# GuitarPedal.net
KiCad netlist of a schematic drawn in Altium Designer
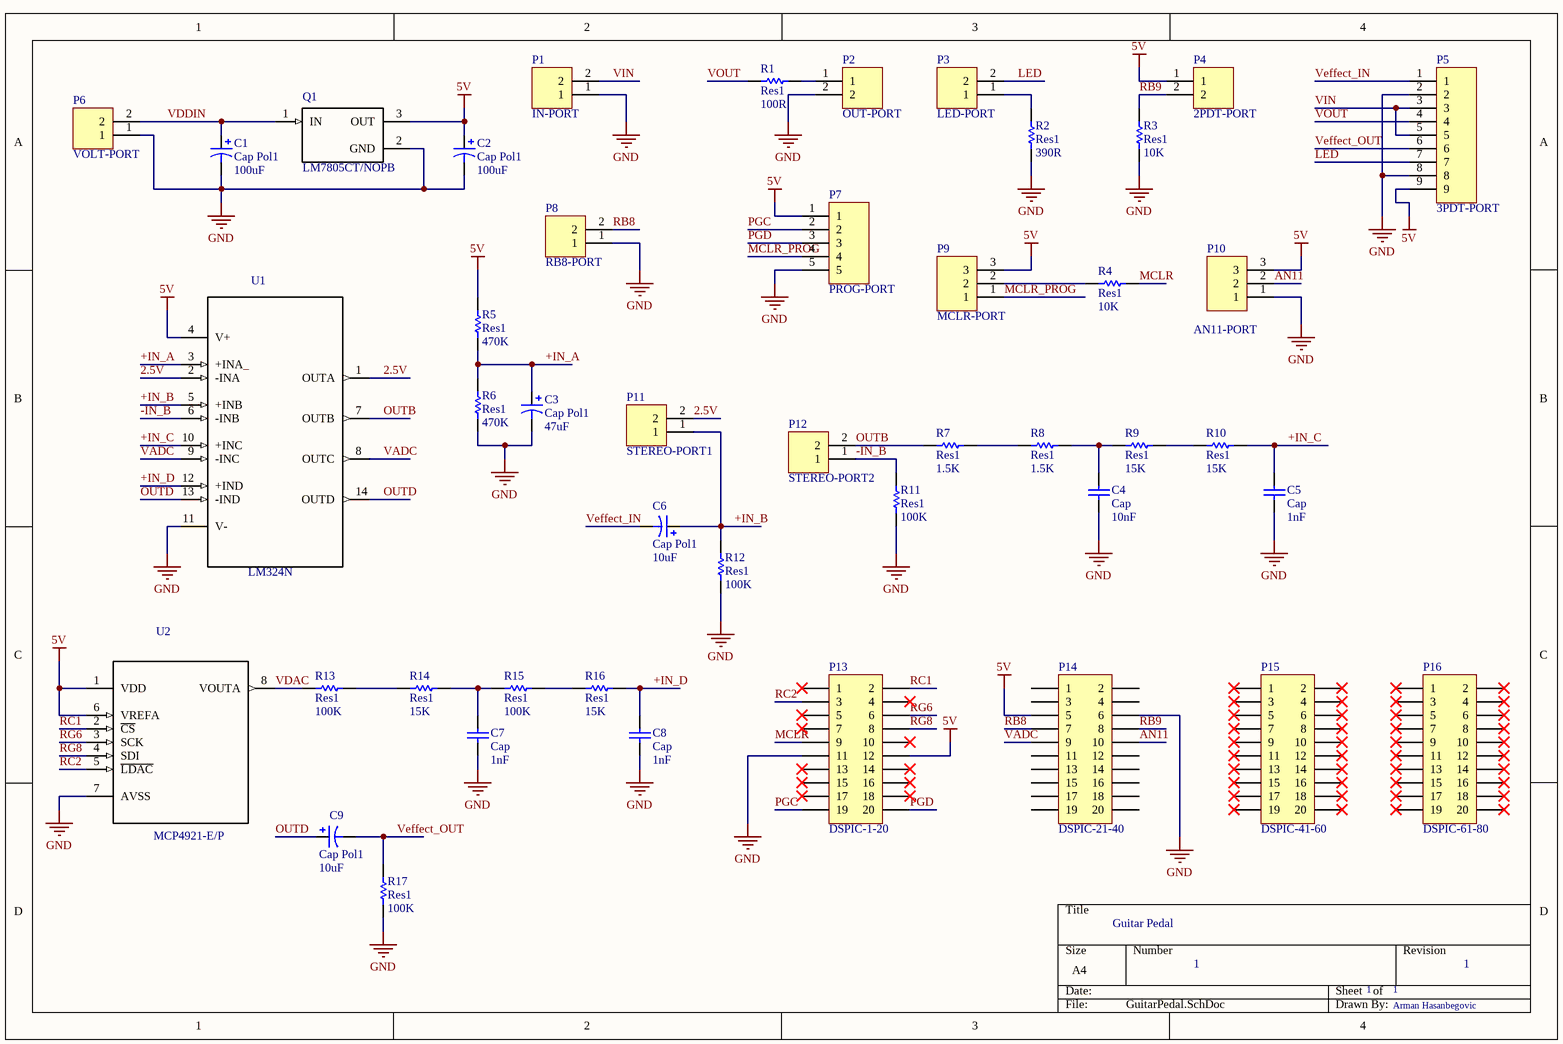
[diagram p0: GuitarPedal.SchDoc]

(export (version "E")
  (design (tool "Eeschema 10.0.6"))
  (components
    (comp (ref "C1")
      (value "Cap Pol1")
      (footprint "RB7.6-15")
      (description "Polarized Capacitor (Radial)")
      (fields (field (name "ALTIUM_VALUE") "100uF") (field (name "PUBLISHER") "Altium Limited"))
      (libsource (lib "Miscellaneous Devices") (part "Cap Pol1"))
    )
    (comp (ref "C2")
      (value "Cap Pol1")
      (footprint "RB7.6-15")
      (description "Polarized Capacitor (Radial)")
      (fields (field (name "ALTIUM_VALUE") "100uF") (field (name "PUBLISHER") "Altium Limited"))
      (libsource (lib "Miscellaneous Devices") (part "Cap Pol1"))
    )
    (comp (ref "C3")
      (value "Cap Pol1")
      (footprint "RB7.6-15")
      (description "Polarized Capacitor (Radial)")
      (fields (field (name "ALTIUM_VALUE") "47uF") (field (name "PUBLISHER") "Altium Limited"))
      (libsource (lib "Miscellaneous Devices") (part "Cap Pol1"))
    )
    (comp (ref "C4")
      (value "Cap")
      (footprint "RAD-0.3")
      (description "Capacitor")
      (fields (field (name "ALTIUM_VALUE") "10nF") (field (name "PUBLISHER") "Altium Limited"))
      (libsource (lib "Miscellaneous Devices") (part "Cap"))
    )
    (comp (ref "C5")
      (value "Cap")
      (footprint "RAD-0.3")
      (description "Capacitor")
      (fields (field (name "ALTIUM_VALUE") "1nF") (field (name "PUBLISHER") "Altium Limited"))
      (libsource (lib "Miscellaneous Devices") (part "Cap"))
    )
    (comp (ref "C6")
      (value "Cap Pol1")
      (footprint "RB7.6-15")
      (description "Polarized Capacitor (Radial)")
      (fields (field (name "ALTIUM_VALUE") "10uF") (field (name "PUBLISHER") "Altium Limited"))
      (libsource (lib "Miscellaneous Devices") (part "Cap Pol1"))
    )
    (comp (ref "C7")
      (value "Cap")
      (footprint "RAD-0.3")
      (description "Capacitor")
      (fields (field (name "ALTIUM_VALUE") "1nF") (field (name "PUBLISHER") "Altium Limited"))
      (libsource (lib "Miscellaneous Devices") (part "Cap"))
    )
    (comp (ref "C8")
      (value "Cap")
      (footprint "RAD-0.3")
      (description "Capacitor")
      (fields (field (name "ALTIUM_VALUE") "1nF") (field (name "PUBLISHER") "Altium Limited"))
      (libsource (lib "Miscellaneous Devices") (part "Cap"))
    )
    (comp (ref "C9")
      (value "Cap Pol1")
      (footprint "RB7.6-15")
      (description "Polarized Capacitor (Radial)")
      (fields (field (name "ALTIUM_VALUE") "10uF") (field (name "PUBLISHER") "Altium Limited"))
      (libsource (lib "Miscellaneous Devices") (part "Cap Pol1"))
    )
    (comp (ref "P1")
      (value "IN-PORT")
      (footprint "HDR1X2")
      (description "Header, 2-Pin")
      (fields (field (name "PUBLISHER") "Altium Limited"))
      (libsource (lib "Miscellaneous Connectors") (part "Header 2"))
    )
    (comp (ref "P2")
      (value "OUT-PORT")
      (footprint "HDR1X2")
      (description "Header, 2-Pin")
      (fields (field (name "PUBLISHER") "Altium Limited"))
      (libsource (lib "") (part "Header 2_1"))
    )
    (comp (ref "P3")
      (value "LED-PORT")
      (footprint "HDR1X2")
      (description "Header, 2-Pin")
      (fields (field (name "PUBLISHER") "Altium Limited"))
      (libsource (lib "Miscellaneous Connectors") (part "Header 2"))
    )
    (comp (ref "P4")
      (value "2PDT-PORT")
      (footprint "HDR1X2")
      (description "Header, 2-Pin")
      (fields (field (name "PUBLISHER") "Altium Limited"))
      (libsource (lib "") (part "Header 2_1"))
    )
    (comp (ref "P5")
      (value "3PDT-PORT")
      (footprint "HDR1X9")
      (description "Header, 9-Pin")
      (fields (field (name "PUBLISHER") "Altium Limited"))
      (libsource (lib "Miscellaneous Connectors") (part "Header 9"))
    )
    (comp (ref "P6")
      (value "VOLT-PORT")
      (footprint "HDR1X2")
      (description "Header, 2-Pin")
      (fields (field (name "PUBLISHER") "Altium Limited"))
      (libsource (lib "Miscellaneous Connectors") (part "Header 2"))
    )
    (comp (ref "P7")
      (value "PROG-PORT")
      (footprint "HDR1X5")
      (description "Header, 5-Pin")
      (fields (field (name "PUBLISHER") "Altium Limited"))
      (libsource (lib "Miscellaneous Connectors") (part "Header 5"))
    )
    (comp (ref "P8")
      (value "RB8-PORT")
      (footprint "HDR1X2")
      (description "Header, 2-Pin")
      (fields (field (name "PUBLISHER") "Altium Limited"))
      (libsource (lib "Miscellaneous Connectors") (part "Header 2"))
    )
    (comp (ref "P9")
      (value "MCLR-PORT")
      (footprint "HDR1X3")
      (description "Header, 3-Pin")
      (fields (field (name "PUBLISHER") "Altium Limited"))
      (libsource (lib "Miscellaneous Connectors") (part "Header 3"))
    )
    (comp (ref "P10")
      (value "AN11-PORT")
      (footprint "HDR1X3")
      (description "Header, 3-Pin")
      (fields (field (name "PUBLISHER") "Altium Limited"))
      (libsource (lib "Miscellaneous Connectors") (part "Header 3"))
    )
    (comp (ref "P11")
      (value "STEREO-PORT1")
      (footprint "HDR1X2")
      (description "Header, 2-Pin")
      (fields (field (name "PUBLISHER") "Altium Limited"))
      (libsource (lib "Miscellaneous Connectors") (part "Header 2"))
    )
    (comp (ref "P12")
      (value "STEREO-PORT2")
      (footprint "HDR1X2")
      (description "Header, 2-Pin")
      (fields (field (name "PUBLISHER") "Altium Limited"))
      (libsource (lib "Miscellaneous Connectors") (part "Header 2"))
    )
    (comp (ref "P13")
      (value "DSPIC-1-20")
      (footprint "HDR2X10")
      (description "Header, 10-Pin, Dual row")
      (fields (field (name "PUBLISHER") "Altium Limited"))
      (libsource (lib "Miscellaneous Connectors") (part "Header 10X2"))
    )
    (comp (ref "P14")
      (value "DSPIC-21-40")
      (footprint "HDR2X10")
      (description "Header, 10-Pin, Dual row")
      (fields (field (name "PUBLISHER") "Altium Limited"))
      (libsource (lib "Miscellaneous Connectors") (part "Header 10X2"))
    )
    (comp (ref "P15")
      (value "DSPIC-41-60")
      (footprint "HDR2X10")
      (description "Header, 10-Pin, Dual row")
      (fields (field (name "PUBLISHER") "Altium Limited"))
      (libsource (lib "Miscellaneous Connectors") (part "Header 10X2"))
    )
    (comp (ref "P16")
      (value "DSPIC-61-80")
      (footprint "HDR2X10")
      (description "Header, 10-Pin, Dual row")
      (fields (field (name "PUBLISHER") "Altium Limited"))
      (libsource (lib "Miscellaneous Connectors") (part "Header 10X2"))
    )
    (comp (ref "Q1")
      (value "LM7805CT/NOPB")
      (footprint "*TO254P1054X470X2600-3")
      (description "IC REG LINEAR 5V 1A TO220AB")
      (fields (field (name "MP") "LM7805CT") (field (name "MF") "ON Semiconductor"))
      (libsource (lib "LM7805CT_NOPB") (part "LM7805CT/NOPB"))
    )
    (comp (ref "R1")
      (value "Res1")
      (footprint "AXIAL-0.3")
      (description "Resistor")
      (fields (field (name "ALTIUM_VALUE") "100R") (field (name "PUBLISHER") "Altium Limited"))
      (libsource (lib "Miscellaneous Devices") (part "Res1"))
    )
    (comp (ref "R2")
      (value "Res1")
      (footprint "AXIAL-0.3")
      (description "Resistor")
      (fields (field (name "ALTIUM_VALUE") "390R") (field (name "PUBLISHER") "Altium Limited"))
      (libsource (lib "Miscellaneous Devices") (part "Res1"))
    )
    (comp (ref "R3")
      (value "Res1")
      (footprint "AXIAL-0.3")
      (description "Resistor")
      (fields (field (name "ALTIUM_VALUE") "10K") (field (name "PUBLISHER") "Altium Limited"))
      (libsource (lib "Miscellaneous Devices") (part "Res1"))
    )
    (comp (ref "R4")
      (value "Res1")
      (footprint "AXIAL-0.3")
      (description "Resistor")
      (fields (field (name "ALTIUM_VALUE") "10K") (field (name "PUBLISHER") "Altium Limited"))
      (libsource (lib "Miscellaneous Devices") (part "Res1"))
    )
    (comp (ref "R5")
      (value "Res1")
      (footprint "AXIAL-0.3")
      (description "Resistor")
      (fields (field (name "ALTIUM_VALUE") "470K") (field (name "PUBLISHER") "Altium Limited"))
      (libsource (lib "Miscellaneous Devices") (part "Res1"))
    )
    (comp (ref "R6")
      (value "Res1")
      (footprint "AXIAL-0.3")
      (description "Resistor")
      (fields (field (name "ALTIUM_VALUE") "470K") (field (name "PUBLISHER") "Altium Limited"))
      (libsource (lib "Miscellaneous Devices") (part "Res1"))
    )
    (comp (ref "R7")
      (value "Res1")
      (footprint "AXIAL-0.3")
      (description "Resistor")
      (fields (field (name "ALTIUM_VALUE") "1.5K") (field (name "PUBLISHER") "Altium Limited"))
      (libsource (lib "Miscellaneous Devices") (part "Res1"))
    )
    (comp (ref "R8")
      (value "Res1")
      (footprint "AXIAL-0.3")
      (description "Resistor")
      (fields (field (name "ALTIUM_VALUE") "1.5K") (field (name "PUBLISHER") "Altium Limited"))
      (libsource (lib "Miscellaneous Devices") (part "Res1"))
    )
    (comp (ref "R9")
      (value "Res1")
      (footprint "AXIAL-0.3")
      (description "Resistor")
      (fields (field (name "ALTIUM_VALUE") "15K") (field (name "PUBLISHER") "Altium Limited"))
      (libsource (lib "Miscellaneous Devices") (part "Res1"))
    )
    (comp (ref "R10")
      (value "Res1")
      (footprint "AXIAL-0.3")
      (description "Resistor")
      (fields (field (name "ALTIUM_VALUE") "15K") (field (name "PUBLISHER") "Altium Limited"))
      (libsource (lib "Miscellaneous Devices") (part "Res1"))
    )
    (comp (ref "R11")
      (value "Res1")
      (footprint "AXIAL-0.3")
      (description "Resistor")
      (fields (field (name "ALTIUM_VALUE") "100K") (field (name "PUBLISHER") "Altium Limited"))
      (libsource (lib "Miscellaneous Devices") (part "Res1"))
    )
    (comp (ref "R12")
      (value "Res1")
      (footprint "AXIAL-0.3")
      (description "Resistor")
      (fields (field (name "ALTIUM_VALUE") "100K") (field (name "PUBLISHER") "Altium Limited"))
      (libsource (lib "Miscellaneous Devices") (part "Res1"))
    )
    (comp (ref "R13")
      (value "Res1")
      (footprint "AXIAL-0.3")
      (description "Resistor")
      (fields (field (name "ALTIUM_VALUE") "100K") (field (name "PUBLISHER") "Altium Limited"))
      (libsource (lib "Miscellaneous Devices") (part "Res1"))
    )
    (comp (ref "R14")
      (value "Res1")
      (footprint "AXIAL-0.3")
      (description "Resistor")
      (fields (field (name "ALTIUM_VALUE") "15K") (field (name "PUBLISHER") "Altium Limited"))
      (libsource (lib "Miscellaneous Devices") (part "Res1"))
    )
    (comp (ref "R15")
      (value "Res1")
      (footprint "AXIAL-0.3")
      (description "Resistor")
      (fields (field (name "ALTIUM_VALUE") "100K") (field (name "PUBLISHER") "Altium Limited"))
      (libsource (lib "Miscellaneous Devices") (part "Res1"))
    )
    (comp (ref "R16")
      (value "Res1")
      (footprint "AXIAL-0.3")
      (description "Resistor")
      (fields (field (name "ALTIUM_VALUE") "15K") (field (name "PUBLISHER") "Altium Limited"))
      (libsource (lib "Miscellaneous Devices") (part "Res1"))
    )
    (comp (ref "R17")
      (value "Res1")
      (footprint "AXIAL-0.3")
      (description "Resistor")
      (fields (field (name "ALTIUM_VALUE") "100K") (field (name "PUBLISHER") "Altium Limited"))
      (libsource (lib "Miscellaneous Devices") (part "Res1"))
    )
    (comp (ref "U1")
      (value "LM324N")
      (footprint "*DIP254P762X508-14")
      (description "Ic Opamp Gp 1.2mhz 14dip")
      (fields (field (name "MF") "STMicroelectronics"))
      (libsource (lib "LM324N") (part "LM324N"))
    )
    (comp (ref "U2")
      (value "MCP4921-E/P")
      (footprint "*DIP254P762X432-8")
      (description "MCP4921 Series 1 Ch 12-Bit Voltage Output Digital-to-Analog Converter-PDIP-8")
      (fields (field (name "DIGI-KEY_PART_NUMBER") "MCP4921-E/P-ND") (field (name "MF") "Microchip"))
      (libsource (lib "MCP4921-E_P") (part "MCP4921-E/P"))
    )
  )
  (nets
    (net (code "1") (name "/+IN_A") (class "Default")
      (node (ref "C3") (pin "1") (pinfunction "1_1") (pintype "passive"))
      (node (ref "R5") (pin "1") (pinfunction "1_1") (pintype "passive"))
      (node (ref "R6") (pin "2") (pinfunction "2_2") (pintype "passive"))
      (node (ref "U1") (pin "3") (pinfunction "+INA__3") (pintype "input"))
    )
    (net (code "2") (name "/+IN_B") (class "Default")
      (node (ref "C6") (pin "1") (pinfunction "1_1") (pintype "passive"))
      (node (ref "P11") (pin "1") (pinfunction "1_1") (pintype "passive"))
      (node (ref "R12") (pin "2") (pinfunction "2_2") (pintype "passive"))
      (node (ref "U1") (pin "5") (pinfunction "+INB_5") (pintype "input"))
    )
    (net (code "3") (name "/+IN_C") (class "Default")
      (node (ref "C5") (pin "2") (pinfunction "2_2") (pintype "passive"))
      (node (ref "R10") (pin "2") (pinfunction "2_2") (pintype "passive"))
      (node (ref "U1") (pin "10") (pinfunction "+INC_10") (pintype "input"))
    )
    (net (code "4") (name "/+IN_D") (class "Default")
      (node (ref "C8") (pin "2") (pinfunction "2_2") (pintype "passive"))
      (node (ref "R16") (pin "2") (pinfunction "2_2") (pintype "passive"))
      (node (ref "U1") (pin "12") (pinfunction "+IND_12") (pintype "input"))
    )
    (net (code "5") (name "/-IN_B") (class "Default")
      (node (ref "P12") (pin "1") (pinfunction "1_1") (pintype "passive"))
      (node (ref "R11") (pin "2") (pinfunction "2_2") (pintype "passive"))
      (node (ref "U1") (pin "6") (pinfunction "-INB_6") (pintype "input"))
    )
    (net (code "6") (name "/2.5V") (class "Default")
      (node (ref "P11") (pin "2") (pinfunction "2_2") (pintype "passive"))
      (node (ref "U1") (pin "1") (pinfunction "OUTA_1") (pintype "output"))
      (node (ref "U1") (pin "2") (pinfunction "-INA_2") (pintype "input"))
    )
    (net (code "7") (name "/AN11") (class "Default")
      (node (ref "P10") (pin "2") (pinfunction "2_2") (pintype "passive"))
      (node (ref "P14") (pin "10") (pinfunction "10_10") (pintype "passive"))
    )
    (net (code "8") (name "/LED") (class "Default")
      (node (ref "P3") (pin "2") (pinfunction "2_2") (pintype "passive"))
      (node (ref "P5") (pin "7") (pinfunction "7_7") (pintype "passive"))
    )
    (net (code "9") (name "/MCLR") (class "Default")
      (node (ref "P13") (pin "9") (pinfunction "9_9") (pintype "passive"))
      (node (ref "R4") (pin "2") (pinfunction "2_2") (pintype "passive"))
    )
    (net (code "10") (name "/MCLR_PROG") (class "Default")
      (node (ref "P7") (pin "4") (pinfunction "4_4") (pintype "passive"))
      (node (ref "P9") (pin "1") (pinfunction "1_1") (pintype "passive"))
    )
    (net (code "11") (name "/OUTB") (class "Default")
      (node (ref "P12") (pin "2") (pinfunction "2_2") (pintype "passive"))
      (node (ref "R7") (pin "1") (pinfunction "1_1") (pintype "passive"))
      (node (ref "U1") (pin "7") (pinfunction "OUTB_7") (pintype "output"))
    )
    (net (code "12") (name "/OUTD") (class "Default")
      (node (ref "C9") (pin "1") (pinfunction "1_1") (pintype "passive"))
      (node (ref "U1") (pin "13") (pinfunction "-IND_13") (pintype "input"))
      (node (ref "U1") (pin "14") (pinfunction "OUTD_14") (pintype "output"))
    )
    (net (code "13") (name "/PGC") (class "Default")
      (node (ref "P13") (pin "19") (pinfunction "19_19") (pintype "passive"))
      (node (ref "P7") (pin "2") (pinfunction "2_2") (pintype "passive"))
    )
    (net (code "14") (name "/PGD") (class "Default")
      (node (ref "P13") (pin "20") (pinfunction "20_20") (pintype "passive"))
      (node (ref "P7") (pin "3") (pinfunction "3_3") (pintype "passive"))
    )
    (net (code "15") (name "/RB8") (class "Default")
      (node (ref "P14") (pin "7") (pinfunction "7_7") (pintype "passive"))
      (node (ref "P8") (pin "2") (pinfunction "2_2") (pintype "passive"))
    )
    (net (code "16") (name "/RB9") (class "Default")
      (node (ref "P14") (pin "8") (pinfunction "8_8") (pintype "passive"))
      (node (ref "P4") (pin "2") (pinfunction "2_2") (pintype "passive"))
      (node (ref "R3") (pin "2") (pinfunction "2_2") (pintype "passive"))
    )
    (net (code "17") (name "/RC1") (class "Default")
      (node (ref "P13") (pin "2") (pinfunction "2_2") (pintype "passive"))
      (node (ref "U2") (pin "2") (pinfunction "~{CS}_2") (pintype "input"))
    )
    (net (code "18") (name "/RC2") (class "Default")
      (node (ref "P13") (pin "3") (pinfunction "3_3") (pintype "passive"))
      (node (ref "U2") (pin "5") (pinfunction "~{LDAC}_5") (pintype "input"))
    )
    (net (code "19") (name "/RG6") (class "Default")
      (node (ref "P13") (pin "6") (pinfunction "6_6") (pintype "passive"))
      (node (ref "U2") (pin "3") (pinfunction "SCK_3") (pintype "input"))
    )
    (net (code "20") (name "/RG8") (class "Default")
      (node (ref "P13") (pin "8") (pinfunction "8_8") (pintype "passive"))
      (node (ref "U2") (pin "4") (pinfunction "SDI_4") (pintype "input"))
    )
    (net (code "21") (name "/VADC") (class "Default")
      (node (ref "P14") (pin "9") (pinfunction "9_9") (pintype "passive"))
      (node (ref "U1") (pin "8") (pinfunction "OUTC_8") (pintype "output"))
      (node (ref "U1") (pin "9") (pinfunction "-INC_9") (pintype "input"))
    )
    (net (code "22") (name "/VDAC") (class "Default")
      (node (ref "R13") (pin "1") (pinfunction "1_1") (pintype "passive"))
      (node (ref "U2") (pin "8") (pinfunction "VOUTA_8") (pintype "output"))
    )
    (net (code "23") (name "/VDDIN") (class "Default")
      (node (ref "C1") (pin "1") (pinfunction "1_1") (pintype "passive"))
      (node (ref "P6") (pin "2") (pinfunction "2_2") (pintype "passive"))
      (node (ref "Q1") (pin "1") (pinfunction "IN_1") (pintype "input"))
    )
    (net (code "24") (name "/VIN") (class "Default")
      (node (ref "P1") (pin "2") (pinfunction "2_2") (pintype "passive"))
      (node (ref "P5") (pin "3") (pinfunction "3_3") (pintype "passive"))
      (node (ref "P5") (pin "5") (pinfunction "5_5") (pintype "passive"))
    )
    (net (code "25") (name "/VOUT") (class "Default")
      (node (ref "P5") (pin "4") (pinfunction "4_4") (pintype "passive"))
      (node (ref "R1") (pin "1") (pinfunction "1_1") (pintype "passive"))
    )
    (net (code "26") (name "/Veffect_IN") (class "Default")
      (node (ref "C6") (pin "2") (pinfunction "2_2") (pintype "passive"))
      (node (ref "P5") (pin "1") (pinfunction "1_1") (pintype "passive"))
    )
    (net (code "27") (name "/Veffect_OUT") (class "Default")
      (node (ref "C9") (pin "2") (pinfunction "2_2") (pintype "passive"))
      (node (ref "P5") (pin "6") (pinfunction "6_6") (pintype "passive"))
      (node (ref "R17") (pin "2") (pinfunction "2_2") (pintype "passive"))
    )
    (net (code "28") (name "5V") (class "Default")
      (node (ref "C2") (pin "1") (pinfunction "1_1") (pintype "passive"))
      (node (ref "P10") (pin "3") (pinfunction "3_3") (pintype "passive"))
      (node (ref "P13") (pin "12") (pinfunction "12_12") (pintype "passive"))
      (node (ref "P14") (pin "5") (pinfunction "5_5") (pintype "passive"))
      (node (ref "P4") (pin "1") (pinfunction "1_1") (pintype "passive"))
      (node (ref "P5") (pin "9") (pinfunction "9_9") (pintype "passive"))
      (node (ref "P7") (pin "1") (pinfunction "1_1") (pintype "passive"))
      (node (ref "P9") (pin "3") (pinfunction "3_3") (pintype "passive"))
      (node (ref "Q1") (pin "3") (pinfunction "OUT_3") (pintype "passive"))
      (node (ref "R5") (pin "2") (pinfunction "2_2") (pintype "passive"))
      (node (ref "U1") (pin "4") (pinfunction "V+_4") (pintype "passive"))
      (node (ref "U2") (pin "1") (pinfunction "VDD_1") (pintype "power_in"))
      (node (ref "U2") (pin "6") (pinfunction "VREFA_6") (pintype "input"))
    )
    (net (code "29") (name "GND") (class "Default")
      (node (ref "C1") (pin "2") (pinfunction "2_2") (pintype "passive"))
      (node (ref "C2") (pin "2") (pinfunction "2_2") (pintype "passive"))
      (node (ref "C3") (pin "2") (pinfunction "2_2") (pintype "passive"))
      (node (ref "C4") (pin "1") (pinfunction "1_1") (pintype "passive"))
      (node (ref "C5") (pin "1") (pinfunction "1_1") (pintype "passive"))
      (node (ref "C7") (pin "1") (pinfunction "1_1") (pintype "passive"))
      (node (ref "C8") (pin "1") (pinfunction "1_1") (pintype "passive"))
      (node (ref "P1") (pin "1") (pinfunction "1_1") (pintype "passive"))
      (node (ref "P10") (pin "1") (pinfunction "1_1") (pintype "passive"))
      (node (ref "P13") (pin "11") (pinfunction "11_11") (pintype "passive"))
      (node (ref "P14") (pin "6") (pinfunction "6_6") (pintype "passive"))
      (node (ref "P2") (pin "2") (pinfunction "2_2") (pintype "passive"))
      (node (ref "P5") (pin "2") (pinfunction "2_2") (pintype "passive"))
      (node (ref "P5") (pin "8") (pinfunction "8_8") (pintype "passive"))
      (node (ref "P6") (pin "1") (pinfunction "1_1") (pintype "passive"))
      (node (ref "P7") (pin "5") (pinfunction "5_5") (pintype "passive"))
      (node (ref "P8") (pin "1") (pinfunction "1_1") (pintype "passive"))
      (node (ref "Q1") (pin "2") (pinfunction "GND_2") (pintype "power_in"))
      (node (ref "R11") (pin "1") (pinfunction "1_1") (pintype "passive"))
      (node (ref "R12") (pin "1") (pinfunction "1_1") (pintype "passive"))
      (node (ref "R17") (pin "1") (pinfunction "1_1") (pintype "passive"))
      (node (ref "R2") (pin "1") (pinfunction "1_1") (pintype "passive"))
      (node (ref "R3") (pin "1") (pinfunction "1_1") (pintype "passive"))
      (node (ref "R6") (pin "1") (pinfunction "1_1") (pintype "passive"))
      (node (ref "U1") (pin "11") (pinfunction "V-_11") (pintype "passive"))
      (node (ref "U2") (pin "7") (pinfunction "AVSS_7") (pintype "passive"))
    )
    (net (code "30") (name "Net-(C4-Pad2)") (class "Default")
      (node (ref "C4") (pin "2") (pinfunction "2_2") (pintype "passive"))
      (node (ref "R8") (pin "2") (pinfunction "2_2") (pintype "passive"))
      (node (ref "R9") (pin "1") (pinfunction "1_1") (pintype "passive"))
    )
    (net (code "31") (name "Net-(C7-Pad2)") (class "Default")
      (node (ref "C7") (pin "2") (pinfunction "2_2") (pintype "passive"))
      (node (ref "R14") (pin "2") (pinfunction "2_2") (pintype "passive"))
      (node (ref "R15") (pin "1") (pinfunction "1_1") (pintype "passive"))
    )
    (net (code "32") (name "Net-(P2-Pad1)") (class "Default")
      (node (ref "P2") (pin "1") (pinfunction "1_1") (pintype "passive"))
      (node (ref "R1") (pin "2") (pinfunction "2_2") (pintype "passive"))
    )
    (net (code "33") (name "Net-(P3-Pad1)") (class "Default")
      (node (ref "P3") (pin "1") (pinfunction "1_1") (pintype "passive"))
      (node (ref "R2") (pin "2") (pinfunction "2_2") (pintype "passive"))
    )
    (net (code "34") (name "Net-(P9-Pad2)") (class "Default")
      (node (ref "P9") (pin "2") (pinfunction "2_2") (pintype "passive"))
      (node (ref "R4") (pin "1") (pinfunction "1_1") (pintype "passive"))
    )
    (net (code "35") (name "Net-(R7-Pad2)") (class "Default")
      (node (ref "R7") (pin "2") (pinfunction "2_2") (pintype "passive"))
      (node (ref "R8") (pin "1") (pinfunction "1_1") (pintype "passive"))
    )
    (net (code "36") (name "Net-(R10-Pad1)") (class "Default")
      (node (ref "R10") (pin "1") (pinfunction "1_1") (pintype "passive"))
      (node (ref "R9") (pin "2") (pinfunction "2_2") (pintype "passive"))
    )
    (net (code "37") (name "Net-(R13-Pad2)") (class "Default")
      (node (ref "R13") (pin "2") (pinfunction "2_2") (pintype "passive"))
      (node (ref "R14") (pin "1") (pinfunction "1_1") (pintype "passive"))
    )
    (net (code "38") (name "Net-(R15-Pad2)") (class "Default")
      (node (ref "R15") (pin "2") (pinfunction "2_2") (pintype "passive"))
      (node (ref "R16") (pin "1") (pinfunction "1_1") (pintype "passive"))
    )
    (net (code "39") (name "unconnected-(P13-Pad1)") (class "Default")
      (node (ref "P13") (pin "1") (pinfunction "1_1") (pintype "passive+no_connect"))
    )
    (net (code "40") (name "unconnected-(P13-Pad4)") (class "Default")
      (node (ref "P13") (pin "4") (pinfunction "4_4") (pintype "passive+no_connect"))
    )
    (net (code "41") (name "unconnected-(P13-Pad5)") (class "Default")
      (node (ref "P13") (pin "5") (pinfunction "5_5") (pintype "passive+no_connect"))
    )
    (net (code "42") (name "unconnected-(P13-Pad7)") (class "Default")
      (node (ref "P13") (pin "7") (pinfunction "7_7") (pintype "passive+no_connect"))
    )
    (net (code "43") (name "unconnected-(P13-Pad10)") (class "Default")
      (node (ref "P13") (pin "10") (pinfunction "10_10") (pintype "passive+no_connect"))
    )
    (net (code "44") (name "unconnected-(P13-Pad13)") (class "Default")
      (node (ref "P13") (pin "13") (pinfunction "13_13") (pintype "passive+no_connect"))
    )
    (net (code "45") (name "unconnected-(P13-Pad14)") (class "Default")
      (node (ref "P13") (pin "14") (pinfunction "14_14") (pintype "passive+no_connect"))
    )
    (net (code "46") (name "unconnected-(P13-Pad15)") (class "Default")
      (node (ref "P13") (pin "15") (pinfunction "15_15") (pintype "passive+no_connect"))
    )
    (net (code "47") (name "unconnected-(P13-Pad16)") (class "Default")
      (node (ref "P13") (pin "16") (pinfunction "16_16") (pintype "passive+no_connect"))
    )
    (net (code "48") (name "unconnected-(P13-Pad17)") (class "Default")
      (node (ref "P13") (pin "17") (pinfunction "17_17") (pintype "passive+no_connect"))
    )
    (net (code "49") (name "unconnected-(P13-Pad18)") (class "Default")
      (node (ref "P13") (pin "18") (pinfunction "18_18") (pintype "passive+no_connect"))
    )
    (net (code "50") (name "unconnected-(P14-Pad1)") (class "Default")
      (node (ref "P14") (pin "1") (pinfunction "1_1") (pintype "passive"))
    )
    (net (code "51") (name "unconnected-(P14-Pad2)") (class "Default")
      (node (ref "P14") (pin "2") (pinfunction "2_2") (pintype "passive"))
    )
    (net (code "52") (name "unconnected-(P14-Pad3)") (class "Default")
      (node (ref "P14") (pin "3") (pinfunction "3_3") (pintype "passive"))
    )
    (net (code "53") (name "unconnected-(P14-Pad4)") (class "Default")
      (node (ref "P14") (pin "4") (pinfunction "4_4") (pintype "passive"))
    )
    (net (code "54") (name "unconnected-(P14-Pad11)") (class "Default")
      (node (ref "P14") (pin "11") (pinfunction "11_11") (pintype "passive"))
    )
    (net (code "55") (name "unconnected-(P14-Pad12)") (class "Default")
      (node (ref "P14") (pin "12") (pinfunction "12_12") (pintype "passive"))
    )
    (net (code "56") (name "unconnected-(P14-Pad13)") (class "Default")
      (node (ref "P14") (pin "13") (pinfunction "13_13") (pintype "passive"))
    )
    (net (code "57") (name "unconnected-(P14-Pad14)") (class "Default")
      (node (ref "P14") (pin "14") (pinfunction "14_14") (pintype "passive"))
    )
    (net (code "58") (name "unconnected-(P14-Pad15)") (class "Default")
      (node (ref "P14") (pin "15") (pinfunction "15_15") (pintype "passive"))
    )
    (net (code "59") (name "unconnected-(P14-Pad16)") (class "Default")
      (node (ref "P14") (pin "16") (pinfunction "16_16") (pintype "passive"))
    )
    (net (code "60") (name "unconnected-(P14-Pad17)") (class "Default")
      (node (ref "P14") (pin "17") (pinfunction "17_17") (pintype "passive"))
    )
    (net (code "61") (name "unconnected-(P14-Pad18)") (class "Default")
      (node (ref "P14") (pin "18") (pinfunction "18_18") (pintype "passive"))
    )
    (net (code "62") (name "unconnected-(P14-Pad19)") (class "Default")
      (node (ref "P14") (pin "19") (pinfunction "19_19") (pintype "passive"))
    )
    (net (code "63") (name "unconnected-(P14-Pad20)") (class "Default")
      (node (ref "P14") (pin "20") (pinfunction "20_20") (pintype "passive"))
    )
    (net (code "64") (name "unconnected-(P15-Pad1)") (class "Default")
      (node (ref "P15") (pin "1") (pinfunction "1_1") (pintype "passive+no_connect"))
    )
    (net (code "65") (name "unconnected-(P15-Pad2)") (class "Default")
      (node (ref "P15") (pin "2") (pinfunction "2_2") (pintype "passive+no_connect"))
    )
    (net (code "66") (name "unconnected-(P15-Pad3)") (class "Default")
      (node (ref "P15") (pin "3") (pinfunction "3_3") (pintype "passive+no_connect"))
    )
    (net (code "67") (name "unconnected-(P15-Pad4)") (class "Default")
      (node (ref "P15") (pin "4") (pinfunction "4_4") (pintype "passive+no_connect"))
    )
    (net (code "68") (name "unconnected-(P15-Pad5)") (class "Default")
      (node (ref "P15") (pin "5") (pinfunction "5_5") (pintype "passive+no_connect"))
    )
    (net (code "69") (name "unconnected-(P15-Pad6)") (class "Default")
      (node (ref "P15") (pin "6") (pinfunction "6_6") (pintype "passive+no_connect"))
    )
    (net (code "70") (name "unconnected-(P15-Pad7)") (class "Default")
      (node (ref "P15") (pin "7") (pinfunction "7_7") (pintype "passive+no_connect"))
    )
    (net (code "71") (name "unconnected-(P15-Pad8)") (class "Default")
      (node (ref "P15") (pin "8") (pinfunction "8_8") (pintype "passive+no_connect"))
    )
    (net (code "72") (name "unconnected-(P15-Pad9)") (class "Default")
      (node (ref "P15") (pin "9") (pinfunction "9_9") (pintype "passive+no_connect"))
    )
    (net (code "73") (name "unconnected-(P15-Pad10)") (class "Default")
      (node (ref "P15") (pin "10") (pinfunction "10_10") (pintype "passive+no_connect"))
    )
    (net (code "74") (name "unconnected-(P15-Pad11)") (class "Default")
      (node (ref "P15") (pin "11") (pinfunction "11_11") (pintype "passive+no_connect"))
    )
    (net (code "75") (name "unconnected-(P15-Pad12)") (class "Default")
      (node (ref "P15") (pin "12") (pinfunction "12_12") (pintype "passive+no_connect"))
    )
    (net (code "76") (name "unconnected-(P15-Pad13)") (class "Default")
      (node (ref "P15") (pin "13") (pinfunction "13_13") (pintype "passive+no_connect"))
    )
    (net (code "77") (name "unconnected-(P15-Pad14)") (class "Default")
      (node (ref "P15") (pin "14") (pinfunction "14_14") (pintype "passive+no_connect"))
    )
    (net (code "78") (name "unconnected-(P15-Pad15)") (class "Default")
      (node (ref "P15") (pin "15") (pinfunction "15_15") (pintype "passive+no_connect"))
    )
    (net (code "79") (name "unconnected-(P15-Pad16)") (class "Default")
      (node (ref "P15") (pin "16") (pinfunction "16_16") (pintype "passive+no_connect"))
    )
    (net (code "80") (name "unconnected-(P15-Pad17)") (class "Default")
      (node (ref "P15") (pin "17") (pinfunction "17_17") (pintype "passive+no_connect"))
    )
    (net (code "81") (name "unconnected-(P15-Pad18)") (class "Default")
      (node (ref "P15") (pin "18") (pinfunction "18_18") (pintype "passive+no_connect"))
    )
    (net (code "82") (name "unconnected-(P15-Pad19)") (class "Default")
      (node (ref "P15") (pin "19") (pinfunction "19_19") (pintype "passive+no_connect"))
    )
    (net (code "83") (name "unconnected-(P15-Pad20)") (class "Default")
      (node (ref "P15") (pin "20") (pinfunction "20_20") (pintype "passive+no_connect"))
    )
    (net (code "84") (name "unconnected-(P16-Pad1)") (class "Default")
      (node (ref "P16") (pin "1") (pinfunction "1_1") (pintype "passive+no_connect"))
    )
    (net (code "85") (name "unconnected-(P16-Pad2)") (class "Default")
      (node (ref "P16") (pin "2") (pinfunction "2_2") (pintype "passive+no_connect"))
    )
    (net (code "86") (name "unconnected-(P16-Pad3)") (class "Default")
      (node (ref "P16") (pin "3") (pinfunction "3_3") (pintype "passive+no_connect"))
    )
    (net (code "87") (name "unconnected-(P16-Pad4)") (class "Default")
      (node (ref "P16") (pin "4") (pinfunction "4_4") (pintype "passive+no_connect"))
    )
    (net (code "88") (name "unconnected-(P16-Pad5)") (class "Default")
      (node (ref "P16") (pin "5") (pinfunction "5_5") (pintype "passive+no_connect"))
    )
    (net (code "89") (name "unconnected-(P16-Pad6)") (class "Default")
      (node (ref "P16") (pin "6") (pinfunction "6_6") (pintype "passive+no_connect"))
    )
    (net (code "90") (name "unconnected-(P16-Pad7)") (class "Default")
      (node (ref "P16") (pin "7") (pinfunction "7_7") (pintype "passive+no_connect"))
    )
    (net (code "91") (name "unconnected-(P16-Pad8)") (class "Default")
      (node (ref "P16") (pin "8") (pinfunction "8_8") (pintype "passive+no_connect"))
    )
    (net (code "92") (name "unconnected-(P16-Pad9)") (class "Default")
      (node (ref "P16") (pin "9") (pinfunction "9_9") (pintype "passive+no_connect"))
    )
    (net (code "93") (name "unconnected-(P16-Pad10)") (class "Default")
      (node (ref "P16") (pin "10") (pinfunction "10_10") (pintype "passive+no_connect"))
    )
    (net (code "94") (name "unconnected-(P16-Pad11)") (class "Default")
      (node (ref "P16") (pin "11") (pinfunction "11_11") (pintype "passive+no_connect"))
    )
    (net (code "95") (name "unconnected-(P16-Pad12)") (class "Default")
      (node (ref "P16") (pin "12") (pinfunction "12_12") (pintype "passive+no_connect"))
    )
    (net (code "96") (name "unconnected-(P16-Pad13)") (class "Default")
      (node (ref "P16") (pin "13") (pinfunction "13_13") (pintype "passive+no_connect"))
    )
    (net (code "97") (name "unconnected-(P16-Pad14)") (class "Default")
      (node (ref "P16") (pin "14") (pinfunction "14_14") (pintype "passive+no_connect"))
    )
    (net (code "98") (name "unconnected-(P16-Pad15)") (class "Default")
      (node (ref "P16") (pin "15") (pinfunction "15_15") (pintype "passive+no_connect"))
    )
    (net (code "99") (name "unconnected-(P16-Pad16)") (class "Default")
      (node (ref "P16") (pin "16") (pinfunction "16_16") (pintype "passive+no_connect"))
    )
    (net (code "100") (name "unconnected-(P16-Pad17)") (class "Default")
      (node (ref "P16") (pin "17") (pinfunction "17_17") (pintype "passive+no_connect"))
    )
    (net (code "101") (name "unconnected-(P16-Pad18)") (class "Default")
      (node (ref "P16") (pin "18") (pinfunction "18_18") (pintype "passive+no_connect"))
    )
    (net (code "102") (name "unconnected-(P16-Pad19)") (class "Default")
      (node (ref "P16") (pin "19") (pinfunction "19_19") (pintype "passive+no_connect"))
    )
    (net (code "103") (name "unconnected-(P16-Pad20)") (class "Default")
      (node (ref "P16") (pin "20") (pinfunction "20_20") (pintype "passive+no_connect"))
    )
  )
)
